# SmartWatch-BASIC-Bottom.net
KiCad netlist of a schematic drawn in EAGLE
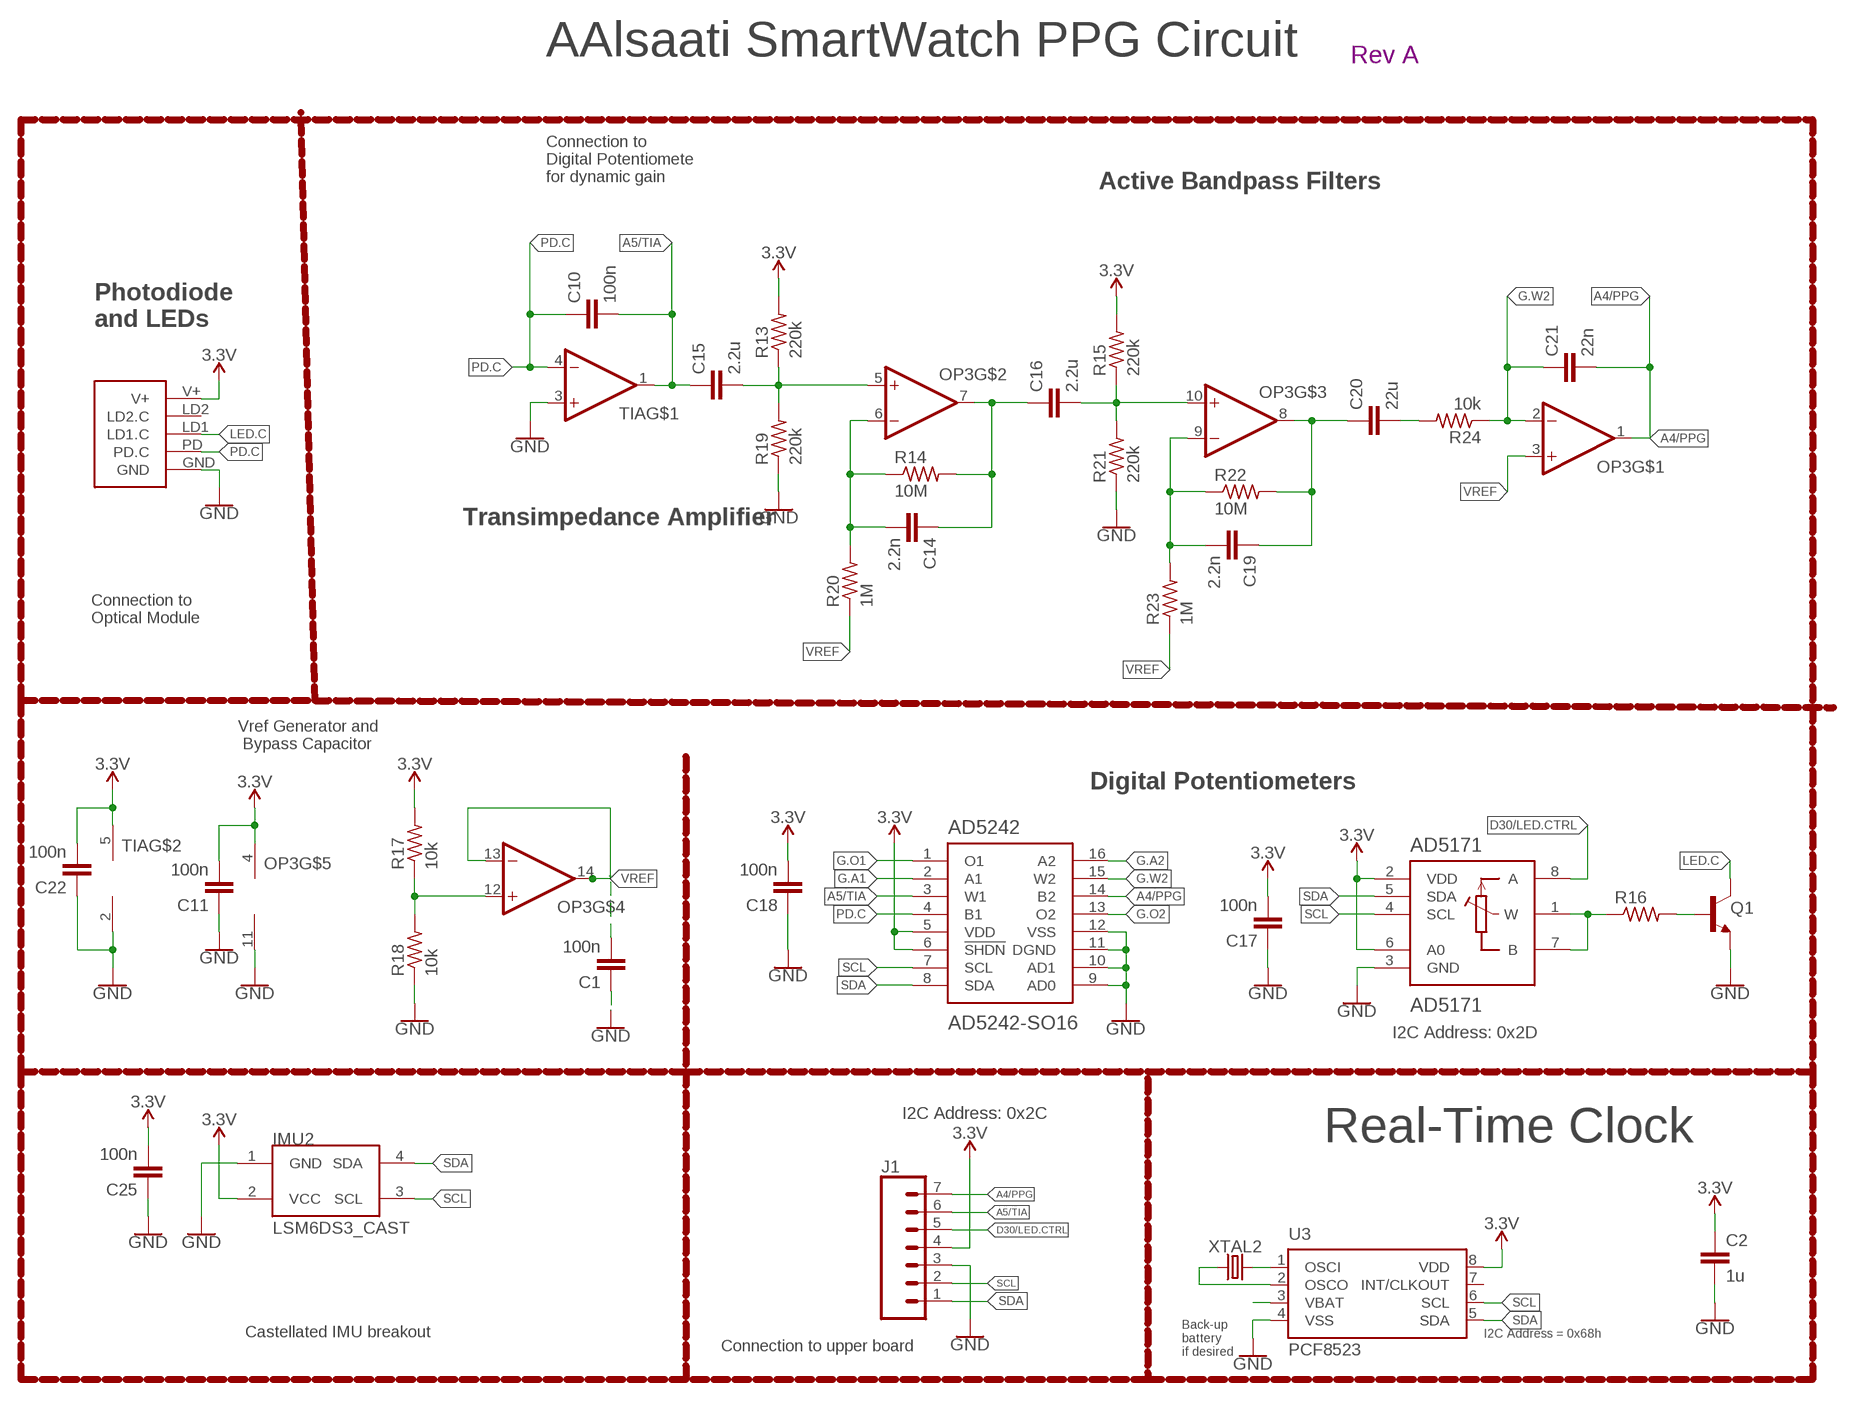
[diagram p0: schematic, sheet 1]

(export (version "E")
  (design (tool "Eeschema 10.0.6"))
  (components
    (comp (ref "AD5171")
      (value "AD5171")
      (footprint "eagle-import:SOT-23-8")
      (libsource (lib "eagle-import") (part "AD5171"))
    )
    (comp (ref "AD5242")
      (value "AD5242-SO16")
      (footprint "eagle-import:SO16")
      (libsource (lib "eagle-import") (part "AD5242-SO16"))
    )
    (comp (ref "C1")
      (value "100n")
      (footprint "eagle-import:C0603")
      (libsource (lib "eagle-import") (part "CAPACITOR0603"))
    )
    (comp (ref "C2")
      (value "1u")
      (footprint "eagle-import:C0603")
      (libsource (lib "eagle-import") (part "CAPACITOR0603"))
    )
    (comp (ref "C10")
      (value "100n")
      (footprint "eagle-import:C0603")
      (libsource (lib "eagle-import") (part "CAPACITOR0603"))
    )
    (comp (ref "C11")
      (value "100n")
      (footprint "eagle-import:C0603")
      (libsource (lib "eagle-import") (part "CAPACITOR0603"))
    )
    (comp (ref "C14")
      (value "2.2n")
      (footprint "eagle-import:C0603")
      (libsource (lib "eagle-import") (part "CAPACITOR0603"))
    )
    (comp (ref "C15")
      (value "2.2u")
      (footprint "eagle-import:C0603")
      (libsource (lib "eagle-import") (part "CAPACITOR0603"))
    )
    (comp (ref "C16")
      (value "2.2u")
      (footprint "eagle-import:C0603")
      (libsource (lib "eagle-import") (part "CAPACITOR0603"))
    )
    (comp (ref "C17")
      (value "100n")
      (footprint "eagle-import:C0603")
      (libsource (lib "eagle-import") (part "CAPACITOR0603"))
    )
    (comp (ref "C18")
      (value "100n")
      (footprint "eagle-import:C0603")
      (libsource (lib "eagle-import") (part "CAPACITOR0603"))
    )
    (comp (ref "C19")
      (value "2.2n")
      (footprint "eagle-import:C0603")
      (libsource (lib "eagle-import") (part "CAPACITOR0603"))
    )
    (comp (ref "C20")
      (value "22u")
      (footprint "eagle-import:C0603")
      (libsource (lib "eagle-import") (part "CAPACITOR0603"))
    )
    (comp (ref "C21")
      (value "22n")
      (footprint "eagle-import:C0603")
      (libsource (lib "eagle-import") (part "CAPACITOR0603"))
    )
    (comp (ref "C22")
      (value "100n")
      (footprint "eagle-import:C0603")
      (libsource (lib "eagle-import") (part "CAPACITOR0603"))
    )
    (comp (ref "C25")
      (value "100n")
      (footprint "eagle-import:C0603")
      (libsource (lib "eagle-import") (part "CAPACITOR0603"))
    )
    (comp (ref "IMU2")
      (value "LSM6DS3_CAST")
      (footprint "eagle-import:LSM6DS3_CAST")
      (libsource (lib "eagle-import") (part "LSM6DS3_CAST"))
    )
    (comp (ref "J1")
      (value "CONN_07-1.27MM")
      (footprint "eagle-import:1X07_1.27MM")
      (libsource (lib "eagle-import") (part "CONN_07-1.27MM"))
    )
    (comp (ref "LOGO1")
      (value "REVISION.A")
      (footprint "eagle-import:REV.A")
      (libsource (lib "eagle-import") (part "REVISION.A"))
    )
    (comp (ref "OP3")
      (value "OP-QUAD-SO14")
      (footprint "eagle-import:SO14")
      (libsource (lib "eagle-import") (part "OP-QUAD-SO14"))
    )
    (comp (ref "Q1")
      (value "NPN-GENERIC")
      (footprint "eagle-import:SOT23-3")
      (libsource (lib "eagle-import") (part "NPN-GENERIC"))
    )
    (comp (ref "R13")
      (value "220k")
      (footprint "eagle-import:R0603")
      (libsource (lib "eagle-import") (part "RESISTOR0603"))
    )
    (comp (ref "R14")
      (value "10M")
      (footprint "eagle-import:R0603")
      (libsource (lib "eagle-import") (part "RESISTOR0603"))
    )
    (comp (ref "R15")
      (value "220k")
      (footprint "eagle-import:R0603")
      (libsource (lib "eagle-import") (part "RESISTOR0603"))
    )
    (comp (ref "R16")
      (value "RESISTOR0603")
      (footprint "eagle-import:R0603")
      (libsource (lib "eagle-import") (part "RESISTOR0603"))
    )
    (comp (ref "R17")
      (value "10k")
      (footprint "eagle-import:R0402")
      (libsource (lib "eagle-import") (part "RESISTOR0402"))
    )
    (comp (ref "R18")
      (value "10k")
      (footprint "eagle-import:R0402")
      (libsource (lib "eagle-import") (part "RESISTOR0402"))
    )
    (comp (ref "R19")
      (value "220k")
      (footprint "eagle-import:R0603")
      (libsource (lib "eagle-import") (part "RESISTOR0603"))
    )
    (comp (ref "R20")
      (value "1M")
      (footprint "eagle-import:R0603")
      (libsource (lib "eagle-import") (part "RESISTOR0603"))
    )
    (comp (ref "R21")
      (value "220k")
      (footprint "eagle-import:R0603")
      (libsource (lib "eagle-import") (part "RESISTOR0603"))
    )
    (comp (ref "R22")
      (value "10M")
      (footprint "eagle-import:R0603")
      (libsource (lib "eagle-import") (part "RESISTOR0603"))
    )
    (comp (ref "R23")
      (value "1M")
      (footprint "eagle-import:R0603")
      (libsource (lib "eagle-import") (part "RESISTOR0603"))
    )
    (comp (ref "R24")
      (value "10k")
      (footprint "eagle-import:R0603")
      (libsource (lib "eagle-import") (part "RESISTOR0603"))
    )
    (comp (ref "TIA")
      (value "OP-SINGLEOT")
      (footprint "eagle-import:SOT23-5")
      (libsource (lib "eagle-import") (part "OP-SINGLEOT"))
    )
    (comp (ref "U$3")
      (value "PPG.MODULE.2")
      (footprint "eagle-import:PPG.MODULE.2")
      (libsource (lib "eagle-import") (part "PPG.MODULE.2"))
    )
    (comp (ref "U3")
      (value "PCF8523")
      (footprint "eagle-import:SO8")
      (libsource (lib "eagle-import") (part "PCF8523"))
    )
    (comp (ref "XTAL2")
      (value "32.7680kHz")
      (footprint "eagle-import:2-SMD.NOLEAD.2.0MMTO1.2MM")
      (fields (field (name "FREQ") "32.7680KHZ"))
      (libsource (lib "eagle-import") (part "CRYSTALECS-.327-12.5-12-C-TR"))
    )
  )
  (nets
    (net (code "1") (name "3.3V") (class "Default")
      (node (ref "AD5171") (pin "2") (pinfunction "VDD_2") (pintype "bidirectional"))
      (node (ref "AD5171") (pin "6") (pinfunction "A0_6") (pintype "bidirectional"))
      (node (ref "AD5242") (pin "5") (pinfunction "VDD_5") (pintype "bidirectional"))
      (node (ref "AD5242") (pin "6") (pinfunction "~{SHDN}_6") (pintype "bidirectional"))
      (node (ref "C11") (pin "2") (pinfunction "2_2") (pintype "passive"))
      (node (ref "C17") (pin "2") (pinfunction "2_2") (pintype "passive"))
      (node (ref "C18") (pin "2") (pinfunction "2_2") (pintype "passive"))
      (node (ref "C2") (pin "1") (pinfunction "1_1") (pintype "passive"))
      (node (ref "C22") (pin "2") (pinfunction "2_2") (pintype "passive"))
      (node (ref "C25") (pin "2") (pinfunction "2_2") (pintype "passive"))
      (node (ref "IMU2") (pin "2") (pinfunction "VCC_2") (pintype "bidirectional"))
      (node (ref "J1") (pin "4") (pinfunction "4_4") (pintype "passive"))
      (node (ref "OP3") (pin "4") (pinfunction "V+_4") (pintype "power_in"))
      (node (ref "R13") (pin "2") (pinfunction "2_2") (pintype "passive"))
      (node (ref "R15") (pin "2") (pinfunction "2_2") (pintype "passive"))
      (node (ref "R17") (pin "2") (pinfunction "2_2") (pintype "passive"))
      (node (ref "TIA") (pin "5") (pinfunction "V+_5") (pintype "power_in"))
      (node (ref "U$3") (pin "V+") (pinfunction "V+_V+") (pintype "bidirectional"))
      (node (ref "U3") (pin "8") (pinfunction "VDD_8") (pintype "power_in"))
    )
    (net (code "2") (name "A4{slash}PPG") (class "Default")
      (node (ref "AD5242") (pin "14") (pinfunction "B2_14") (pintype "bidirectional"))
      (node (ref "C21") (pin "2") (pinfunction "2_2") (pintype "passive"))
      (node (ref "J1") (pin "7") (pinfunction "7_7") (pintype "passive"))
      (node (ref "OP3") (pin "1") (pinfunction "OUT_1") (pintype "output"))
    )
    (net (code "3") (name "A5{slash}TIA") (class "Default")
      (node (ref "AD5242") (pin "3") (pinfunction "W1_3") (pintype "bidirectional"))
      (node (ref "C10") (pin "2") (pinfunction "2_2") (pintype "passive"))
      (node (ref "C15") (pin "1") (pinfunction "1_1") (pintype "passive"))
      (node (ref "J1") (pin "6") (pinfunction "6_6") (pintype "passive"))
      (node (ref "TIA") (pin "1") (pinfunction "OUT_1") (pintype "output"))
    )
    (net (code "4") (name "D30{slash}LED.CTRL") (class "Default")
      (node (ref "AD5171") (pin "8") (pinfunction "A_8") (pintype "bidirectional"))
      (node (ref "J1") (pin "5") (pinfunction "5_5") (pintype "passive"))
    )
    (net (code "5") (name "G.A1") (class "Default")
      (node (ref "AD5242") (pin "2") (pinfunction "A1_2") (pintype "bidirectional"))
    )
    (net (code "6") (name "G.A2") (class "Default")
      (node (ref "AD5242") (pin "16") (pinfunction "A2_16") (pintype "bidirectional"))
    )
    (net (code "7") (name "G.O1") (class "Default")
      (node (ref "AD5242") (pin "1") (pinfunction "O1_1") (pintype "bidirectional"))
    )
    (net (code "8") (name "G.O2") (class "Default")
      (node (ref "AD5242") (pin "13") (pinfunction "O2_13") (pintype "bidirectional"))
    )
    (net (code "9") (name "G.W2") (class "Default")
      (node (ref "AD5242") (pin "15") (pinfunction "W2_15") (pintype "bidirectional"))
      (node (ref "C21") (pin "1") (pinfunction "1_1") (pintype "passive"))
      (node (ref "OP3") (pin "2") (pinfunction "-IN_2") (pintype "input"))
      (node (ref "R24") (pin "1") (pinfunction "1_1") (pintype "passive"))
    )
    (net (code "10") (name "GND") (class "Default")
      (node (ref "AD5171") (pin "3") (pinfunction "GND_3") (pintype "bidirectional"))
      (node (ref "AD5242") (pin "10") (pinfunction "AD1_10") (pintype "bidirectional"))
      (node (ref "AD5242") (pin "11") (pinfunction "DGND_11") (pintype "bidirectional"))
      (node (ref "AD5242") (pin "12") (pinfunction "VSS_12") (pintype "bidirectional"))
      (node (ref "AD5242") (pin "9") (pinfunction "AD0_9") (pintype "bidirectional"))
      (node (ref "C1") (pin "1") (pinfunction "1_1") (pintype "passive"))
      (node (ref "C11") (pin "1") (pinfunction "1_1") (pintype "passive"))
      (node (ref "C17") (pin "1") (pinfunction "1_1") (pintype "passive"))
      (node (ref "C18") (pin "1") (pinfunction "1_1") (pintype "passive"))
      (node (ref "C2") (pin "2") (pinfunction "2_2") (pintype "passive"))
      (node (ref "C22") (pin "1") (pinfunction "1_1") (pintype "passive"))
      (node (ref "C25") (pin "1") (pinfunction "1_1") (pintype "passive"))
      (node (ref "IMU2") (pin "1") (pinfunction "GND_1") (pintype "bidirectional"))
      (node (ref "J1") (pin "3") (pinfunction "3_3") (pintype "passive"))
      (node (ref "OP3") (pin "11") (pinfunction "V-_11") (pintype "power_in"))
      (node (ref "Q1") (pin "2") (pinfunction "E_2") (pintype "passive"))
      (node (ref "R18") (pin "1") (pinfunction "1_1") (pintype "passive"))
      (node (ref "R19") (pin "1") (pinfunction "1_1") (pintype "passive"))
      (node (ref "R21") (pin "1") (pinfunction "1_1") (pintype "passive"))
      (node (ref "TIA") (pin "2") (pinfunction "V-_2") (pintype "power_in"))
      (node (ref "TIA") (pin "3") (pinfunction "+IN_3") (pintype "input"))
      (node (ref "U$3") (pin "GND") (pinfunction "GND_GND") (pintype "bidirectional"))
      (node (ref "U3") (pin "4") (pinfunction "VSS_4") (pintype "power_in"))
    )
    (net (code "11") (name "LED.C") (class "Default")
      (node (ref "Q1") (pin "3") (pinfunction "C_3") (pintype "passive"))
      (node (ref "U$3") (pin "LD1") (pinfunction "LD1.C_LD1") (pintype "bidirectional"))
    )
    (net (code "12") (name "Net-(AD5171-B)") (class "Default")
      (node (ref "AD5171") (pin "1") (pinfunction "W_1") (pintype "bidirectional"))
      (node (ref "AD5171") (pin "7") (pinfunction "B_7") (pintype "bidirectional"))
      (node (ref "R16") (pin "1") (pinfunction "1_1") (pintype "passive"))
    )
    (net (code "13") (name "Net-(C20-Pad2)") (class "Default")
      (node (ref "C20") (pin "2") (pinfunction "2_2") (pintype "passive"))
      (node (ref "R24") (pin "2") (pinfunction "2_2") (pintype "passive"))
    )
    (net (code "14") (name "Net-(OP3B-+IN)") (class "Default")
      (node (ref "C15") (pin "2") (pinfunction "2_2") (pintype "passive"))
      (node (ref "OP3") (pin "5") (pinfunction "+IN_5") (pintype "input"))
      (node (ref "R13") (pin "1") (pinfunction "1_1") (pintype "passive"))
      (node (ref "R19") (pin "2") (pinfunction "2_2") (pintype "passive"))
    )
    (net (code "15") (name "Net-(OP3B--IN)") (class "Default")
      (node (ref "C14") (pin "2") (pinfunction "2_2") (pintype "passive"))
      (node (ref "OP3") (pin "6") (pinfunction "-IN_6") (pintype "input"))
      (node (ref "R14") (pin "1") (pinfunction "1_1") (pintype "passive"))
      (node (ref "R20") (pin "2") (pinfunction "2_2") (pintype "passive"))
    )
    (net (code "16") (name "Net-(OP3B-OUT)") (class "Default")
      (node (ref "C14") (pin "1") (pinfunction "1_1") (pintype "passive"))
      (node (ref "C16") (pin "1") (pinfunction "1_1") (pintype "passive"))
      (node (ref "OP3") (pin "7") (pinfunction "OUT_7") (pintype "output"))
      (node (ref "R14") (pin "2") (pinfunction "2_2") (pintype "passive"))
    )
    (net (code "17") (name "Net-(OP3C-+IN)") (class "Default")
      (node (ref "C16") (pin "2") (pinfunction "2_2") (pintype "passive"))
      (node (ref "OP3") (pin "10") (pinfunction "+IN_10") (pintype "input"))
      (node (ref "R15") (pin "1") (pinfunction "1_1") (pintype "passive"))
      (node (ref "R21") (pin "2") (pinfunction "2_2") (pintype "passive"))
    )
    (net (code "18") (name "Net-(OP3C--IN)") (class "Default")
      (node (ref "C19") (pin "2") (pinfunction "2_2") (pintype "passive"))
      (node (ref "OP3") (pin "9") (pinfunction "-IN_9") (pintype "input"))
      (node (ref "R22") (pin "1") (pinfunction "1_1") (pintype "passive"))
      (node (ref "R23") (pin "2") (pinfunction "2_2") (pintype "passive"))
    )
    (net (code "19") (name "Net-(OP3C-OUT)") (class "Default")
      (node (ref "C19") (pin "1") (pinfunction "1_1") (pintype "passive"))
      (node (ref "C20") (pin "1") (pinfunction "1_1") (pintype "passive"))
      (node (ref "OP3") (pin "8") (pinfunction "OUT_8") (pintype "output"))
      (node (ref "R22") (pin "2") (pinfunction "2_2") (pintype "passive"))
    )
    (net (code "20") (name "Net-(OP3D-+IN)") (class "Default")
      (node (ref "OP3") (pin "12") (pinfunction "+IN_12") (pintype "input"))
      (node (ref "R17") (pin "1") (pinfunction "1_1") (pintype "passive"))
      (node (ref "R18") (pin "2") (pinfunction "2_2") (pintype "passive"))
    )
    (net (code "21") (name "Net-(Q1-B)") (class "Default")
      (node (ref "Q1") (pin "1") (pinfunction "B_1") (pintype "passive"))
      (node (ref "R16") (pin "2") (pinfunction "2_2") (pintype "passive"))
    )
    (net (code "22") (name "Net-(U3-OSCI)") (class "Default")
      (node (ref "U3") (pin "1") (pinfunction "OSCI_1") (pintype "bidirectional"))
      (node (ref "XTAL2") (pin "P$2") (pinfunction "2_P$2") (pintype "passive"))
    )
    (net (code "23") (name "Net-(U3-OSCO)") (class "Default")
      (node (ref "U3") (pin "2") (pinfunction "OSCO_2") (pintype "bidirectional"))
      (node (ref "XTAL2") (pin "P$1") (pinfunction "1_P$1") (pintype "passive"))
    )
    (net (code "24") (name "PD.C") (class "Default")
      (node (ref "AD5242") (pin "4") (pinfunction "B1_4") (pintype "bidirectional"))
      (node (ref "C10") (pin "1") (pinfunction "1_1") (pintype "passive"))
      (node (ref "TIA") (pin "4") (pinfunction "-IN_4") (pintype "input"))
      (node (ref "U$3") (pin "PD") (pinfunction "PD.C_PD") (pintype "bidirectional"))
    )
    (net (code "25") (name "SCL") (class "Default")
      (node (ref "AD5171") (pin "4") (pinfunction "SCL_4") (pintype "bidirectional"))
      (node (ref "AD5242") (pin "7") (pinfunction "SCL_7") (pintype "bidirectional"))
      (node (ref "IMU2") (pin "3") (pinfunction "SCL_3") (pintype "bidirectional"))
      (node (ref "J1") (pin "2") (pinfunction "2_2") (pintype "passive"))
      (node (ref "U3") (pin "6") (pinfunction "SCL_6") (pintype "bidirectional"))
    )
    (net (code "26") (name "SDA") (class "Default")
      (node (ref "AD5171") (pin "5") (pinfunction "SDA_5") (pintype "bidirectional"))
      (node (ref "AD5242") (pin "8") (pinfunction "SDA_8") (pintype "bidirectional"))
      (node (ref "IMU2") (pin "4") (pinfunction "SDA_4") (pintype "bidirectional"))
      (node (ref "J1") (pin "1") (pinfunction "1_1") (pintype "passive"))
      (node (ref "U3") (pin "5") (pinfunction "SDA_5") (pintype "bidirectional"))
    )
    (net (code "27") (name "VREF") (class "Default")
      (node (ref "C1") (pin "2") (pinfunction "2_2") (pintype "passive"))
      (node (ref "OP3") (pin "13") (pinfunction "-IN_13") (pintype "input"))
      (node (ref "OP3") (pin "14") (pinfunction "OUT_14") (pintype "output"))
      (node (ref "OP3") (pin "3") (pinfunction "+IN_3") (pintype "input"))
      (node (ref "R20") (pin "1") (pinfunction "1_1") (pintype "passive"))
      (node (ref "R23") (pin "1") (pinfunction "1_1") (pintype "passive"))
    )
    (net (code "28") (name "unconnected-(U$3-LD2.C-PadLD2)") (class "Default")
      (node (ref "U$3") (pin "LD2") (pinfunction "LD2.C_LD2") (pintype "bidirectional"))
    )
    (net (code "29") (name "unconnected-(U3-INT{slash}CLKOUT-Pad7)") (class "Default")
      (node (ref "U3") (pin "7") (pinfunction "INT/CLKOUT_7") (pintype "bidirectional"))
    )
    (net (code "30") (name "unconnected-(U3-VBAT-Pad3)") (class "Default")
      (node (ref "U3") (pin "3") (pinfunction "VBAT_3") (pintype "power_in"))
    )
  )
)
